# pickit2.net
KiCad netlist of a schematic drawn in EAGLE
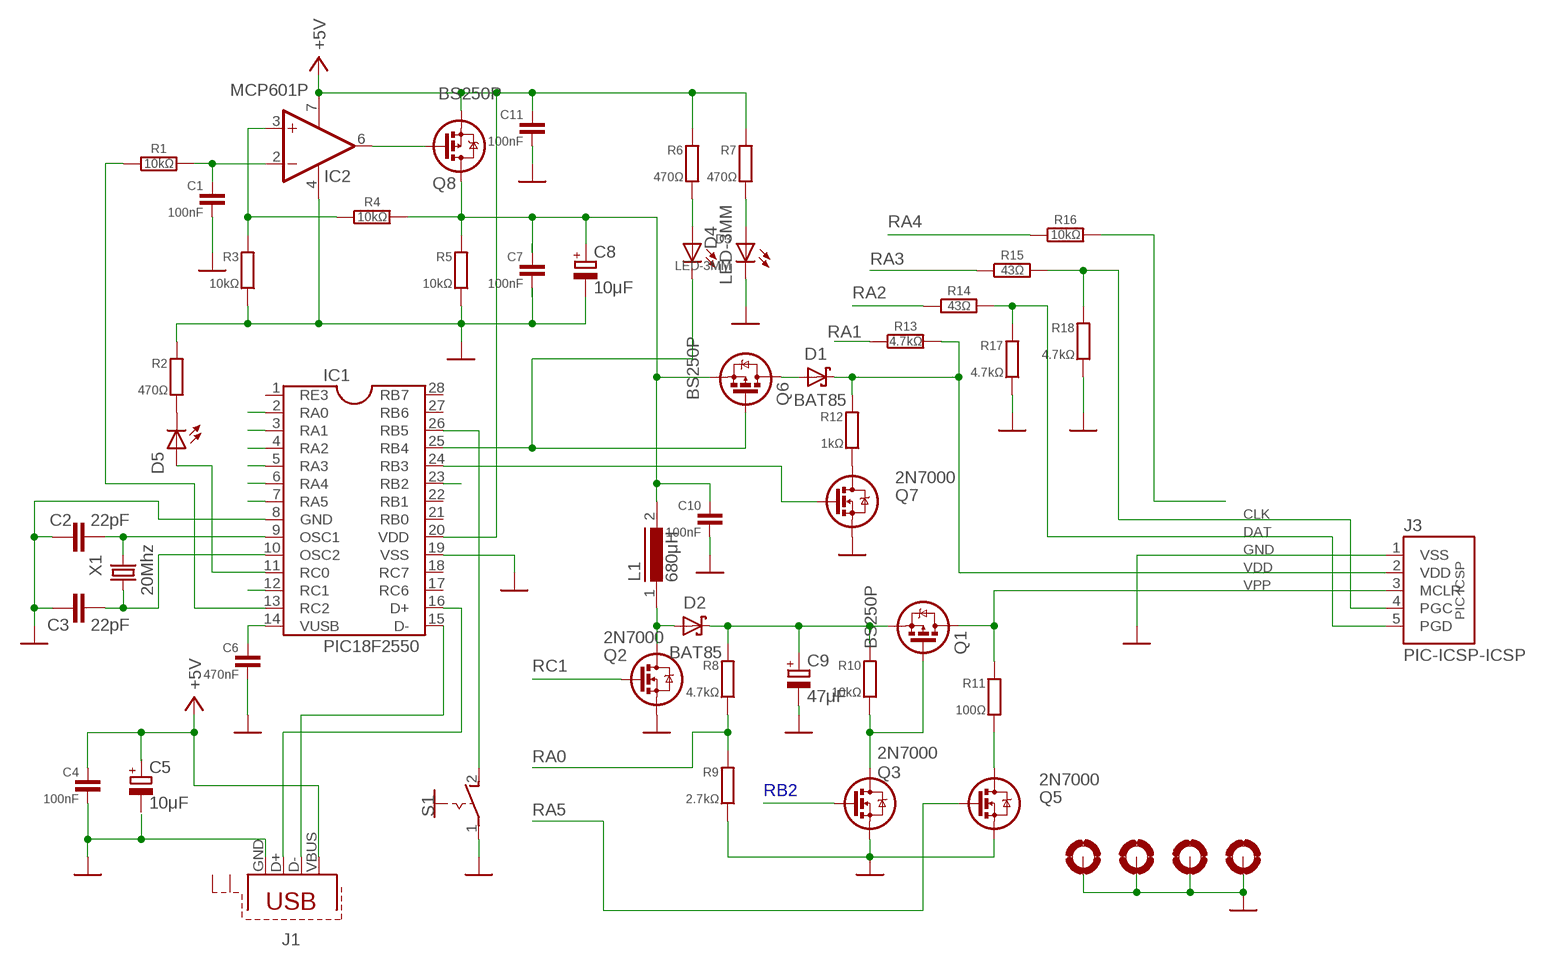
[diagram p0: schematic, sheet 1]

(export (version "E")
  (design (tool "Eeschema 10.0.6"))
  (components
    (comp (ref "C1")
      (value "100nF")
      (footprint "eagle-import:C050-025X075_V")
      (libsource (lib "eagle-import") (part "C050-025X075/V"))
    )
    (comp (ref "C2")
      (value "22pF")
      (footprint "eagle-import:C2.5-2")
      (libsource (lib "eagle-import") (part "C2.5/2"))
    )
    (comp (ref "C3")
      (value "22pF")
      (footprint "eagle-import:C2.5-2")
      (libsource (lib "eagle-import") (part "C2.5/2"))
    )
    (comp (ref "C4")
      (value "100nF")
      (footprint "eagle-import:C050-025X075_V")
      (libsource (lib "eagle-import") (part "C050-025X075/V"))
    )
    (comp (ref "C5")
      (value "10μF")
      (footprint "eagle-import:E2,5-5")
      (libsource (lib "eagle-import") (part "CPOLE2.5-5"))
    )
    (comp (ref "C6")
      (value "470nF")
      (footprint "eagle-import:C050-025X075_V")
      (libsource (lib "eagle-import") (part "C050-025X075/V"))
    )
    (comp (ref "C7")
      (value "100nF")
      (footprint "eagle-import:C050-025X075_V")
      (libsource (lib "eagle-import") (part "C050-025X075/V"))
    )
    (comp (ref "C8")
      (value "10μF")
      (footprint "eagle-import:E2,5-5")
      (libsource (lib "eagle-import") (part "CPOLE2.5-5"))
    )
    (comp (ref "C9")
      (value "47μF")
      (footprint "eagle-import:E2,5-5")
      (libsource (lib "eagle-import") (part "CPOLE2.5-5"))
    )
    (comp (ref "C10")
      (value "100nF")
      (footprint "eagle-import:C050-025X075_V")
      (libsource (lib "eagle-import") (part "C050-025X075/V"))
    )
    (comp (ref "C11")
      (value "100nF")
      (footprint "eagle-import:C050-025X075_V")
      (libsource (lib "eagle-import") (part "C050-025X075/V"))
    )
    (comp (ref "D1")
      (value "BAT85")
      (footprint "eagle-import:DO35-10M")
      (libsource (lib "eagle-import") (part "BAT42M"))
    )
    (comp (ref "D2")
      (value "BAT85")
      (footprint "eagle-import:DO35-10M")
      (libsource (lib "eagle-import") (part "BAT42M"))
    )
    (comp (ref "D3")
      (value "LED-3MM")
      (footprint "eagle-import:LED_3MM")
      (libsource (lib "eagle-import") (part "LED-3MM"))
    )
    (comp (ref "D4")
      (value "LED-3MM")
      (footprint "eagle-import:LED_3MM")
      (libsource (lib "eagle-import") (part "LED-3MM"))
    )
    (comp (ref "D5")
      (value "LED5MM")
      (footprint "eagle-import:LED5MM")
      (libsource (lib "eagle-import") (part "LED5MM"))
    )
    (comp (ref "H1")
      (value "MOUNT-PAD-ROUND2.8")
      (footprint "eagle-import:2,8-PAD")
      (libsource (lib "eagle-import") (part "MOUNT-PAD-ROUND2.8"))
    )
    (comp (ref "H2")
      (value "MOUNT-PAD-ROUND2.8")
      (footprint "eagle-import:2,8-PAD")
      (libsource (lib "eagle-import") (part "MOUNT-PAD-ROUND2.8"))
    )
    (comp (ref "H3")
      (value "MOUNT-PAD-ROUND2.8")
      (footprint "eagle-import:2,8-PAD")
      (libsource (lib "eagle-import") (part "MOUNT-PAD-ROUND2.8"))
    )
    (comp (ref "H4")
      (value "MOUNT-PAD-ROUND2.8")
      (footprint "eagle-import:2,8-PAD")
      (libsource (lib "eagle-import") (part "MOUNT-PAD-ROUND2.8"))
    )
    (comp (ref "IC1")
      (value "PIC18F2550")
      (footprint "eagle-import:DIL28")
      (libsource (lib "eagle-import") (part "PIC18F2550"))
    )
    (comp (ref "IC2")
      (value "MCP601P")
      (footprint "eagle-import:DIL08M")
      (libsource (lib "eagle-import") (part "MCP601M"))
    )
    (comp (ref "J1")
      (value "PN61729-S")
      (footprint "eagle-import:PN61729-S")
      (libsource (lib "eagle-import") (part "PN61729-S"))
    )
    (comp (ref "J3")
      (value "PIC-ICSP-ICSP")
      (footprint "eagle-import:PIC-ICSP")
      (libsource (lib "eagle-import") (part "PIC-ICSP-ICSP"))
    )
    (comp (ref "L1")
      (value "680μH")
      (footprint "eagle-import:R0608")
      (libsource (lib "eagle-import") (part "82114RM"))
    )
    (comp (ref "Q1")
      (value "BS250P")
      (footprint "eagle-import:TO92")
      (libsource (lib "eagle-import") (part "BS250P"))
    )
    (comp (ref "Q2")
      (value "2N7000")
      (footprint "eagle-import:TO92")
      (libsource (lib "eagle-import") (part "2N7000"))
    )
    (comp (ref "Q3")
      (value "2N7000")
      (footprint "eagle-import:TO92")
      (libsource (lib "eagle-import") (part "2N7000"))
    )
    (comp (ref "Q5")
      (value "2N7000")
      (footprint "eagle-import:TO92")
      (libsource (lib "eagle-import") (part "2N7000"))
    )
    (comp (ref "Q6")
      (value "BS250P")
      (footprint "eagle-import:TO92")
      (libsource (lib "eagle-import") (part "BS250P"))
    )
    (comp (ref "Q7")
      (value "2N7000")
      (footprint "eagle-import:TO92")
      (libsource (lib "eagle-import") (part "2N7000"))
    )
    (comp (ref "Q8")
      (value "BS250P")
      (footprint "eagle-import:TO92")
      (libsource (lib "eagle-import") (part "BS250P"))
    )
    (comp (ref "R1")
      (value "10kΩ")
      (footprint "eagle-import:0204_10")
      (libsource (lib "eagle-import") (part "R-H0204/10"))
    )
    (comp (ref "R2")
      (value "470Ω")
      (footprint "eagle-import:0204_10")
      (libsource (lib "eagle-import") (part "R0204/10"))
    )
    (comp (ref "R3")
      (value "10kΩ")
      (footprint "eagle-import:0204_10")
      (libsource (lib "eagle-import") (part "R0204/10"))
    )
    (comp (ref "R4")
      (value "10kΩ")
      (footprint "eagle-import:0204_10")
      (libsource (lib "eagle-import") (part "R-H0204/10"))
    )
    (comp (ref "R5")
      (value "10kΩ")
      (footprint "eagle-import:0204_10")
      (libsource (lib "eagle-import") (part "R0204/10"))
    )
    (comp (ref "R6")
      (value "470Ω")
      (footprint "eagle-import:0204_10")
      (libsource (lib "eagle-import") (part "R0204/10"))
    )
    (comp (ref "R7")
      (value "470Ω")
      (footprint "eagle-import:0204_10")
      (libsource (lib "eagle-import") (part "R0204/10"))
    )
    (comp (ref "R8")
      (value "4.7kΩ")
      (footprint "eagle-import:0204_10")
      (libsource (lib "eagle-import") (part "R0204/10"))
    )
    (comp (ref "R9")
      (value "2.7kΩ")
      (footprint "eagle-import:0204_10")
      (libsource (lib "eagle-import") (part "R0204/10"))
    )
    (comp (ref "R10")
      (value "10kΩ")
      (footprint "eagle-import:0204_10")
      (libsource (lib "eagle-import") (part "R0204/10"))
    )
    (comp (ref "R11")
      (value "100Ω")
      (footprint "eagle-import:0204_10")
      (libsource (lib "eagle-import") (part "R0204/10"))
    )
    (comp (ref "R12")
      (value "1kΩ")
      (footprint "eagle-import:0204_10")
      (libsource (lib "eagle-import") (part "R0204/10"))
    )
    (comp (ref "R13")
      (value "4.7kΩ")
      (footprint "eagle-import:0204_10")
      (libsource (lib "eagle-import") (part "R-H0204/10"))
    )
    (comp (ref "R14")
      (value "43Ω")
      (footprint "eagle-import:0204_10")
      (libsource (lib "eagle-import") (part "R-H0204/10"))
    )
    (comp (ref "R15")
      (value "43Ω")
      (footprint "eagle-import:0204_10")
      (libsource (lib "eagle-import") (part "R-H0204/10"))
    )
    (comp (ref "R16")
      (value "10kΩ")
      (footprint "eagle-import:0204_10")
      (libsource (lib "eagle-import") (part "R-H0204/10"))
    )
    (comp (ref "R17")
      (value "4.7kΩ")
      (footprint "eagle-import:0204_10")
      (libsource (lib "eagle-import") (part "R0204/10"))
    )
    (comp (ref "R18")
      (value "4.7kΩ")
      (footprint "eagle-import:0204_10")
      (libsource (lib "eagle-import") (part "R0204/10"))
    )
    (comp (ref "S1")
      (value "PB-1P-1T")
      (footprint "eagle-import:PB-1P1T")
      (libsource (lib "eagle-import") (part "PB-1P-1T"))
    )
    (comp (ref "X1")
      (value "20Mhz")
      (footprint "eagle-import:HC49")
      (libsource (lib "eagle-import") (part "CRYSTALHC49"))
    )
  )
  (nets
    (net (code "1") (name "+5V") (class "Default")
      (node (ref "C11") (pin "1") (pinfunction "1_1") (pintype "passive"))
      (node (ref "C4") (pin "1") (pinfunction "1_1") (pintype "passive"))
      (node (ref "C5") (pin "+") (pinfunction "+_+") (pintype "passive"))
      (node (ref "IC1") (pin "20") (pinfunction "VDD_20") (pintype "power_in"))
      (node (ref "IC2") (pin "7") (pinfunction "V+_7") (pintype "power_in"))
      (node (ref "J1") (pin "VBUS") (pinfunction "1_VBUS") (pintype "passive"))
      (node (ref "Q8") (pin "3") (pinfunction "S_3") (pintype "passive"))
      (node (ref "R6") (pin "1") (pinfunction "1_1") (pintype "passive"))
      (node (ref "R7") (pin "1") (pinfunction "1_1") (pintype "passive"))
    )
    (net (code "2") (name "/RA0") (class "Default")
      (node (ref "IC1") (pin "2") (pinfunction "RA0_2") (pintype "bidirectional"))
      (node (ref "R8") (pin "2") (pinfunction "2_2") (pintype "passive"))
      (node (ref "R9") (pin "1") (pinfunction "1_1") (pintype "passive"))
    )
    (net (code "3") (name "/RA1") (class "Default")
      (node (ref "IC1") (pin "3") (pinfunction "RA1_3") (pintype "bidirectional"))
      (node (ref "R13") (pin "1") (pinfunction "1_1") (pintype "passive"))
    )
    (net (code "4") (name "/RA2") (class "Default")
      (node (ref "IC1") (pin "4") (pinfunction "RA2_4") (pintype "bidirectional"))
      (node (ref "R14") (pin "1") (pinfunction "1_1") (pintype "passive"))
    )
    (net (code "5") (name "/RA3") (class "Default")
      (node (ref "IC1") (pin "5") (pinfunction "RA3_5") (pintype "bidirectional"))
      (node (ref "R15") (pin "1") (pinfunction "1_1") (pintype "passive"))
    )
    (net (code "6") (name "/RA4") (class "Default")
      (node (ref "IC1") (pin "6") (pinfunction "RA4_6") (pintype "bidirectional"))
      (node (ref "R16") (pin "1") (pinfunction "1_1") (pintype "passive"))
    )
    (net (code "7") (name "/RA5") (class "Default")
      (node (ref "IC1") (pin "7") (pinfunction "RA5_7") (pintype "bidirectional"))
      (node (ref "Q5") (pin "2") (pinfunction "G_2") (pintype "passive"))
    )
    (net (code "8") (name "/RB2") (class "Default")
      (node (ref "IC1") (pin "23") (pinfunction "RB2_23") (pintype "bidirectional"))
      (node (ref "Q3") (pin "2") (pinfunction "G_2") (pintype "passive"))
    )
    (net (code "9") (name "/RC1") (class "Default")
      (node (ref "IC1") (pin "12") (pinfunction "RC1_12") (pintype "bidirectional"))
      (node (ref "Q2") (pin "2") (pinfunction "G_2") (pintype "passive"))
    )
    (net (code "10") (name "GND") (class "Default")
      (node (ref "C1") (pin "2") (pinfunction "2_2") (pintype "passive"))
      (node (ref "C10") (pin "2") (pinfunction "2_2") (pintype "passive"))
      (node (ref "C11") (pin "2") (pinfunction "2_2") (pintype "passive"))
      (node (ref "C2") (pin "1") (pinfunction "1_1") (pintype "passive"))
      (node (ref "C3") (pin "2") (pinfunction "2_2") (pintype "passive"))
      (node (ref "C4") (pin "2") (pinfunction "2_2") (pintype "passive"))
      (node (ref "C6") (pin "2") (pinfunction "2_2") (pintype "passive"))
      (node (ref "C7") (pin "2") (pinfunction "2_2") (pintype "passive"))
      (node (ref "C8") (pin "-") (pinfunction "-_-") (pintype "passive"))
      (node (ref "C9") (pin "-") (pinfunction "-_-") (pintype "passive"))
      (node (ref "D3") (pin "K") (pinfunction "C_K") (pintype "passive"))
      (node (ref "H1") (pin "B2,8") (pinfunction "MOUNT_B2,8") (pintype "passive"))
      (node (ref "H2") (pin "B2,8") (pinfunction "MOUNT_B2,8") (pintype "passive"))
      (node (ref "H3") (pin "B2,8") (pinfunction "MOUNT_B2,8") (pintype "passive"))
      (node (ref "H4") (pin "B2,8") (pinfunction "MOUNT_B2,8") (pintype "passive"))
      (node (ref "IC1") (pin "19") (pinfunction "VSS_19") (pintype "power_in"))
      (node (ref "IC1") (pin "8") (pinfunction "GND_8") (pintype "power_in"))
      (node (ref "IC2") (pin "4") (pinfunction "V-_4") (pintype "power_in"))
      (node (ref "J1") (pin "GND") (pinfunction "4_GND") (pintype "passive"))
      (node (ref "J3") (pin "1") (pinfunction "VSS_1") (pintype "passive"))
      (node (ref "Q2") (pin "1") (pinfunction "S_1") (pintype "passive"))
      (node (ref "Q3") (pin "1") (pinfunction "S_1") (pintype "passive"))
      (node (ref "Q5") (pin "1") (pinfunction "S_1") (pintype "passive"))
      (node (ref "Q7") (pin "1") (pinfunction "S_1") (pintype "passive"))
      (node (ref "R17") (pin "2") (pinfunction "2_2") (pintype "passive"))
      (node (ref "R18") (pin "2") (pinfunction "2_2") (pintype "passive"))
      (node (ref "R2") (pin "1") (pinfunction "1_1") (pintype "passive"))
      (node (ref "R3") (pin "2") (pinfunction "2_2") (pintype "passive"))
      (node (ref "R5") (pin "2") (pinfunction "2_2") (pintype "passive"))
      (node (ref "R9") (pin "2") (pinfunction "2_2") (pintype "passive"))
      (node (ref "S1") (pin "1") (pinfunction "P_1") (pintype "passive"))
    )
    (net (code "11") (name "Net-(D3-PadA)") (class "Default")
      (node (ref "D3") (pin "A") (pinfunction "A_A") (pintype "passive"))
      (node (ref "R7") (pin "2") (pinfunction "2_2") (pintype "passive"))
    )
    (net (code "12") (name "Net-(D4-C)") (class "Default")
      (node (ref "D4") (pin "K") (pinfunction "C_K") (pintype "passive"))
      (node (ref "IC1") (pin "25") (pinfunction "RB4_25") (pintype "bidirectional"))
      (node (ref "Q6") (pin "2") (pinfunction "G_2") (pintype "passive"))
    )
    (net (code "13") (name "Net-(D4-PadA)") (class "Default")
      (node (ref "D4") (pin "A") (pinfunction "A_A") (pintype "passive"))
      (node (ref "R6") (pin "2") (pinfunction "2_2") (pintype "passive"))
    )
    (net (code "14") (name "Net-(D5-C)") (class "Default")
      (node (ref "D5") (pin "K") (pinfunction "C_K") (pintype "passive"))
      (node (ref "R2") (pin "2") (pinfunction "2_2") (pintype "passive"))
    )
    (net (code "15") (name "Net-(IC1-D+)") (class "Default")
      (node (ref "IC1") (pin "16") (pinfunction "D+_16") (pintype "bidirectional"))
      (node (ref "J1") (pin "D+") (pinfunction "3_D+") (pintype "passive"))
    )
    (net (code "16") (name "Net-(IC1-D-)") (class "Default")
      (node (ref "IC1") (pin "15") (pinfunction "D-_15") (pintype "bidirectional"))
      (node (ref "J1") (pin "D-") (pinfunction "2_D-") (pintype "passive"))
    )
    (net (code "17") (name "Net-(IC1-OSC1)") (class "Default")
      (node (ref "C2") (pin "2") (pinfunction "2_2") (pintype "passive"))
      (node (ref "IC1") (pin "9") (pinfunction "OSC1_9") (pintype "bidirectional"))
      (node (ref "X1") (pin "2") (pinfunction "2_2") (pintype "passive"))
    )
    (net (code "18") (name "Net-(IC1-OSC2)") (class "Default")
      (node (ref "C3") (pin "1") (pinfunction "1_1") (pintype "passive"))
      (node (ref "IC1") (pin "10") (pinfunction "OSC2_10") (pintype "bidirectional"))
      (node (ref "X1") (pin "1") (pinfunction "1_1") (pintype "passive"))
    )
    (net (code "19") (name "Net-(IC1-RB3)") (class "Default")
      (node (ref "IC1") (pin "24") (pinfunction "RB3_24") (pintype "bidirectional"))
      (node (ref "Q7") (pin "2") (pinfunction "G_2") (pintype "passive"))
    )
    (net (code "20") (name "Net-(IC1-RB5)") (class "Default")
      (node (ref "IC1") (pin "26") (pinfunction "RB5_26") (pintype "bidirectional"))
      (node (ref "S1") (pin "2") (pinfunction "S_2") (pintype "passive"))
    )
    (net (code "21") (name "Net-(IC1-RC0)") (class "Default")
      (node (ref "D5") (pin "A") (pinfunction "A_A") (pintype "passive"))
      (node (ref "IC1") (pin "11") (pinfunction "RC0_11") (pintype "bidirectional"))
    )
    (net (code "22") (name "Net-(IC1-RC2)") (class "Default")
      (node (ref "IC1") (pin "13") (pinfunction "RC2_13") (pintype "bidirectional"))
      (node (ref "R1") (pin "1") (pinfunction "1_1") (pintype "passive"))
    )
    (net (code "23") (name "Net-(IC1-VUSB)") (class "Default")
      (node (ref "C6") (pin "1") (pinfunction "1_1") (pintype "passive"))
      (node (ref "IC1") (pin "14") (pinfunction "VUSB_14") (pintype "bidirectional"))
    )
    (net (code "24") (name "Net-(IC2-+IN)") (class "Default")
      (node (ref "IC2") (pin "3") (pinfunction "+IN_3") (pintype "input"))
      (node (ref "R3") (pin "1") (pinfunction "1_1") (pintype "passive"))
      (node (ref "R4") (pin "1") (pinfunction "1_1") (pintype "passive"))
    )
    (net (code "25") (name "Net-(IC2--IN)") (class "Default")
      (node (ref "C1") (pin "1") (pinfunction "1_1") (pintype "passive"))
      (node (ref "IC2") (pin "2") (pinfunction "-IN_2") (pintype "input"))
      (node (ref "R1") (pin "2") (pinfunction "2_2") (pintype "passive"))
    )
    (net (code "26") (name "Net-(IC2-OUT)") (class "Default")
      (node (ref "IC2") (pin "6") (pinfunction "OUT_6") (pintype "output"))
      (node (ref "Q8") (pin "2") (pinfunction "G_2") (pintype "passive"))
    )
    (net (code "27") (name "Net-(J3-MCLR)") (class "Default")
      (node (ref "J3") (pin "3") (pinfunction "MCLR_3") (pintype "passive"))
      (node (ref "Q1") (pin "1") (pinfunction "D_1") (pintype "passive"))
      (node (ref "R11") (pin "1") (pinfunction "1_1") (pintype "passive"))
    )
    (net (code "28") (name "Net-(J3-PGC)") (class "Default")
      (node (ref "J3") (pin "4") (pinfunction "PGC_4") (pintype "passive"))
      (node (ref "R15") (pin "2") (pinfunction "2_2") (pintype "passive"))
      (node (ref "R18") (pin "1") (pinfunction "1_1") (pintype "passive"))
    )
    (net (code "29") (name "Net-(J3-PGD)") (class "Default")
      (node (ref "J3") (pin "5") (pinfunction "PGD_5") (pintype "passive"))
      (node (ref "R14") (pin "2") (pinfunction "2_2") (pintype "passive"))
      (node (ref "R17") (pin "1") (pinfunction "1_1") (pintype "passive"))
    )
    (net (code "30") (name "Net-(J3-VDD)") (class "Default")
      (node (ref "D1") (pin "C") (pinfunction "C_C") (pintype "passive"))
      (node (ref "J3") (pin "2") (pinfunction "VDD_2") (pintype "passive"))
      (node (ref "R12") (pin "1") (pinfunction "1_1") (pintype "passive"))
      (node (ref "R13") (pin "2") (pinfunction "2_2") (pintype "passive"))
    )
    (net (code "31") (name "Net-(Q1-G)") (class "Default")
      (node (ref "Q1") (pin "2") (pinfunction "G_2") (pintype "passive"))
      (node (ref "Q3") (pin "3") (pinfunction "D_3") (pintype "passive"))
      (node (ref "R10") (pin "2") (pinfunction "2_2") (pintype "passive"))
    )
    (net (code "32") (name "Net-(Q1-S)") (class "Default")
      (node (ref "C9") (pin "+") (pinfunction "+_+") (pintype "passive"))
      (node (ref "D2") (pin "C") (pinfunction "C_C") (pintype "passive"))
      (node (ref "Q1") (pin "3") (pinfunction "S_3") (pintype "passive"))
      (node (ref "R10") (pin "1") (pinfunction "1_1") (pintype "passive"))
      (node (ref "R8") (pin "1") (pinfunction "1_1") (pintype "passive"))
    )
    (net (code "33") (name "Net-(Q2-D)") (class "Default")
      (node (ref "D2") (pin "A") (pinfunction "A_A") (pintype "passive"))
      (node (ref "L1") (pin "1") (pinfunction "1_1") (pintype "passive"))
      (node (ref "Q2") (pin "3") (pinfunction "D_3") (pintype "passive"))
    )
    (net (code "34") (name "Net-(Q5-D)") (class "Default")
      (node (ref "Q5") (pin "3") (pinfunction "D_3") (pintype "passive"))
      (node (ref "R11") (pin "2") (pinfunction "2_2") (pintype "passive"))
    )
    (net (code "35") (name "Net-(Q6-D)") (class "Default")
      (node (ref "D1") (pin "A") (pinfunction "A_A") (pintype "passive"))
      (node (ref "Q6") (pin "1") (pinfunction "D_1") (pintype "passive"))
    )
    (net (code "36") (name "Net-(Q6-S)") (class "Default")
      (node (ref "C10") (pin "1") (pinfunction "1_1") (pintype "passive"))
      (node (ref "C7") (pin "1") (pinfunction "1_1") (pintype "passive"))
      (node (ref "C8") (pin "+") (pinfunction "+_+") (pintype "passive"))
      (node (ref "L1") (pin "2") (pinfunction "2_2") (pintype "passive"))
      (node (ref "Q6") (pin "3") (pinfunction "S_3") (pintype "passive"))
      (node (ref "Q8") (pin "1") (pinfunction "D_1") (pintype "passive"))
      (node (ref "R4") (pin "2") (pinfunction "2_2") (pintype "passive"))
      (node (ref "R5") (pin "1") (pinfunction "1_1") (pintype "passive"))
    )
    (net (code "37") (name "Net-(Q7-D)") (class "Default")
      (node (ref "Q7") (pin "3") (pinfunction "D_3") (pintype "passive"))
      (node (ref "R12") (pin "2") (pinfunction "2_2") (pintype "passive"))
    )
    (net (code "38") (name "unconnected-(C5-Pad-)") (class "Default")
      (node (ref "C5") (pin "-") (pinfunction "-_-") (pintype "passive"))
    )
    (net (code "39") (name "unconnected-(IC1-RB0-Pad21)") (class "Default")
      (node (ref "IC1") (pin "21") (pinfunction "RB0_21") (pintype "bidirectional"))
    )
    (net (code "40") (name "unconnected-(IC1-RB1-Pad22)") (class "Default")
      (node (ref "IC1") (pin "22") (pinfunction "RB1_22") (pintype "bidirectional"))
    )
    (net (code "41") (name "unconnected-(IC1-RB6-Pad27)") (class "Default")
      (node (ref "IC1") (pin "27") (pinfunction "RB6_27") (pintype "bidirectional"))
    )
    (net (code "42") (name "unconnected-(IC1-RB7-Pad28)") (class "Default")
      (node (ref "IC1") (pin "28") (pinfunction "RB7_28") (pintype "bidirectional"))
    )
    (net (code "43") (name "unconnected-(IC1-RC6-Pad17)") (class "Default")
      (node (ref "IC1") (pin "17") (pinfunction "RC6_17") (pintype "bidirectional"))
    )
    (net (code "44") (name "unconnected-(IC1-RC7-Pad18)") (class "Default")
      (node (ref "IC1") (pin "18") (pinfunction "RC7_18") (pintype "bidirectional"))
    )
    (net (code "45") (name "unconnected-(IC1-RE3-Pad1)") (class "Default")
      (node (ref "IC1") (pin "1") (pinfunction "RE3_1") (pintype "bidirectional"))
    )
    (net (code "46") (name "unconnected-(J1-PadS1)") (class "Default")
      (node (ref "J1") (pin "S1") (pinfunction "S1_S1") (pintype "passive"))
    )
    (net (code "47") (name "unconnected-(J1-PadS2)") (class "Default")
      (node (ref "J1") (pin "S2") (pinfunction "S2_S2") (pintype "passive"))
    )
    (net (code "48") (name "unconnected-(R16-Pad2)") (class "Default")
      (node (ref "R16") (pin "2") (pinfunction "2_2") (pintype "passive"))
    )
  )
)
